# Main.net
KiCad netlist of a schematic drawn in Altium Designer
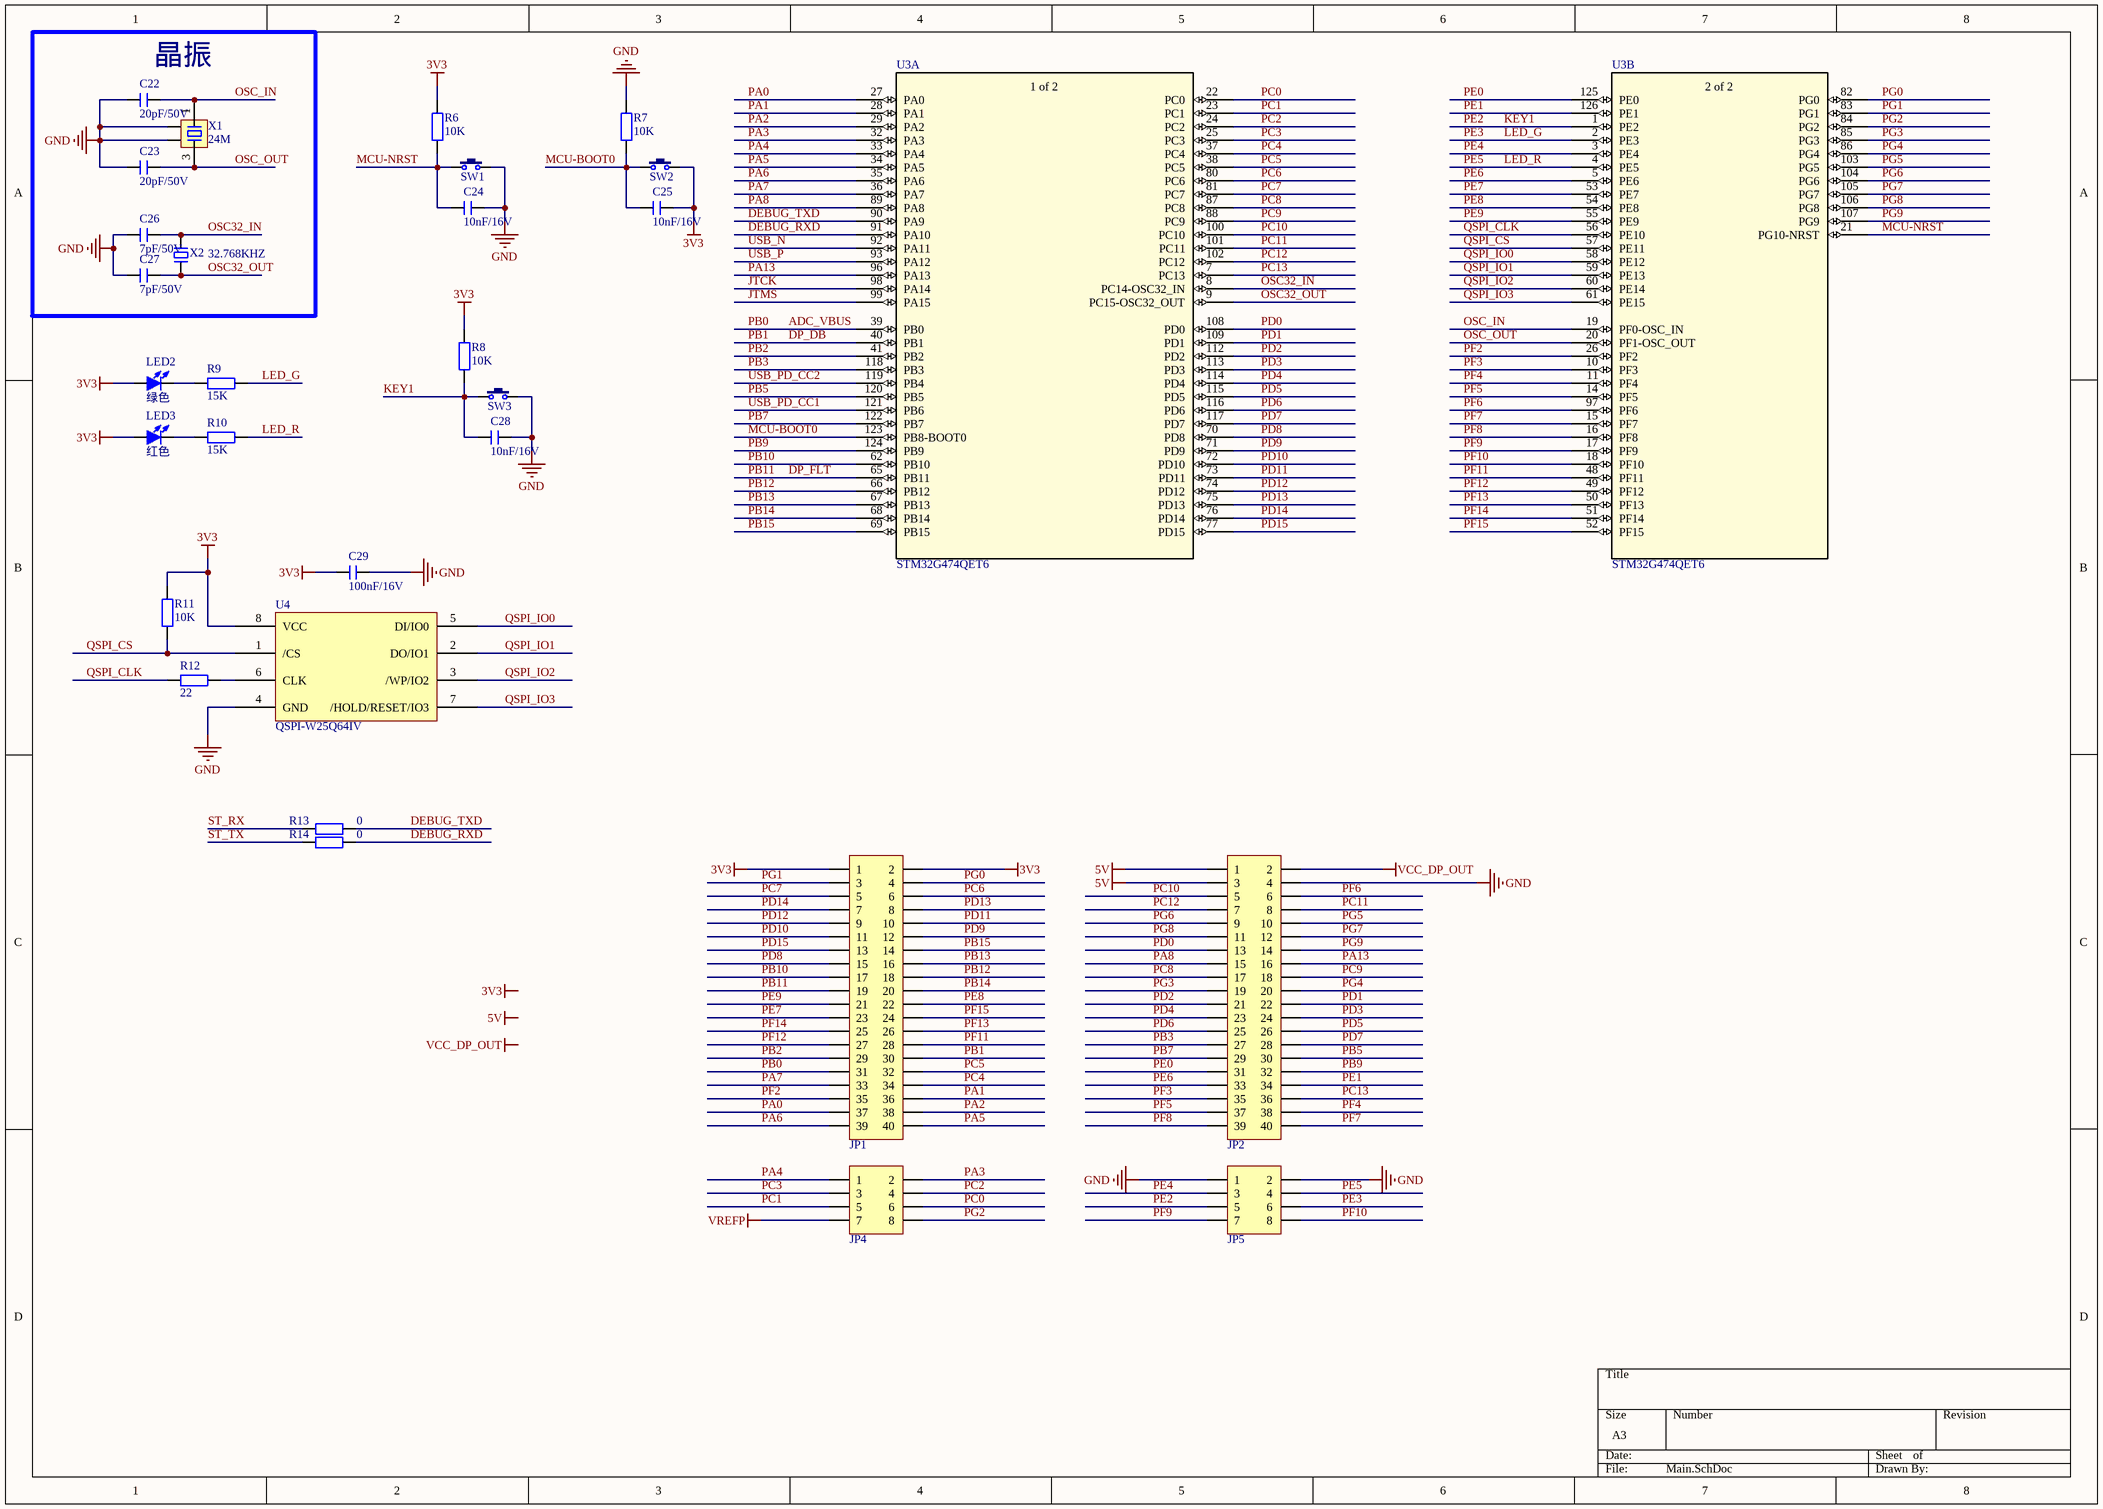
[diagram p0: Main.SchDoc]

(export (version "E")
  (design (tool "Eeschema 10.0.6"))
  (components
    (comp (ref "C22")
      (value "20pF/50V")
      (footprint "C 0402_L")
      (description "贴片电容")
      (libsource (lib "3.1   - 电阻-电容-电感") (part "C"))
    )
    (comp (ref "C23")
      (value "20pF/50V")
      (footprint "C 0402_L")
      (description "贴片电容")
      (libsource (lib "3.1   - 电阻-电容-电感") (part "C"))
    )
    (comp (ref "C24")
      (value "10nF/16V")
      (footprint "C 0402_L")
      (description "贴片电容")
      (libsource (lib "3.1   - 电阻-电容-电感") (part "C"))
    )
    (comp (ref "C25")
      (value "10nF/16V")
      (footprint "C 0402_L")
      (description "贴片电容")
      (libsource (lib "3.1   - 电阻-电容-电感") (part "C"))
    )
    (comp (ref "C26")
      (value "7pF/50V")
      (footprint "C 0402_L")
      (description "贴片电容")
      (libsource (lib "3.1   - 电阻-电容-电感") (part "C"))
    )
    (comp (ref "C27")
      (value "7pF/50V")
      (footprint "C 0402_L")
      (description "贴片电容")
      (libsource (lib "3.1   - 电阻-电容-电感") (part "C"))
    )
    (comp (ref "C28")
      (value "10nF/16V")
      (footprint "C 0402_L")
      (description "贴片电容")
      (libsource (lib "3.1   - 电阻-电容-电感") (part "C"))
    )
    (comp (ref "C29")
      (value "100nF/16V")
      (footprint "C 0402_L")
      (description "贴片电容")
      (libsource (lib "3.1   - 电阻-电容-电感") (part "C"))
    )
    (comp (ref "JP1")
      (value "Header 2X11")
      (footprint "HDR2.54-LI-2x20P")
      (description "20*2P接插件")
      (fields (field (name "版权归属") "源创客"))
      (libsource (lib "4.5   - 接插件-脚距2.54") (part "Header 20X2"))
    )
    (comp (ref "JP2")
      (value "Header 2X11")
      (footprint "HDR2.54-LI-2x20P")
      (description "20*2P接插件")
      (fields (field (name "版权归属") "源创客"))
      (libsource (lib "4.5   - 接插件-脚距2.54") (part "Header 20X2"))
    )
    (comp (ref "JP4")
      (value "Header 4X2")
      (footprint "HDR2.54-LI-2x4P")
      (description "4*2P接插件")
      (fields (field (name "版权归属") "源创客"))
      (libsource (lib "4.5   - 接插件-脚距2.54") (part "Header 4X2"))
    )
    (comp (ref "JP5")
      (value "Header 4X2")
      (footprint "HDR2.54-LI-2x4P")
      (description "4*2P接插件")
      (fields (field (name "版权归属") "源创客"))
      (libsource (lib "4.5   - 接插件-脚距2.54") (part "Header 4X2"))
    )
    (comp (ref "LED2")
      (value "绿色")
      (footprint "LED")
      (description "C84267")
      (libsource (lib "9.1   - LED") (part "LED-SMD"))
    )
    (comp (ref "LED3")
      (value "红色")
      (footprint "LED")
      (description "C84267")
      (libsource (lib "9.1   - LED") (part "LED-SMD"))
    )
    (comp (ref "R6")
      (value "10K")
      (footprint "R 0402_L")
      (description "贴片电阻")
      (libsource (lib "3.1   - 电阻-电容-电感") (part "R"))
    )
    (comp (ref "R7")
      (value "10K")
      (footprint "R 0402_L")
      (description "贴片电阻")
      (libsource (lib "3.1   - 电阻-电容-电感") (part "R"))
    )
    (comp (ref "R8")
      (value "10K")
      (footprint "R 0402_L")
      (description "贴片电阻")
      (libsource (lib "3.1   - 电阻-电容-电感") (part "R"))
    )
    (comp (ref "R9")
      (value "15K")
      (footprint "R 0402_L")
      (description "贴片电阻 0402 5%")
      (libsource (lib "3.1   - 电阻-电容-电感") (part "R"))
    )
    (comp (ref "R10")
      (value "15K")
      (footprint "R 0402_L")
      (description "贴片电阻 0402 5%")
      (libsource (lib "3.1   - 电阻-电容-电感") (part "R"))
    )
    (comp (ref "R11")
      (value "10K")
      (footprint "R 0402_L")
      (description "贴片电阻 0402 1%")
      (libsource (lib "3.1   - 电阻-电容-电感") (part "R"))
    )
    (comp (ref "R12")
      (value "22")
      (footprint "R 0402_L")
      (description "贴片电阻 0402 1%")
      (libsource (lib "3.1   - 电阻-电容-电感") (part "R"))
    )
    (comp (ref "R13")
      (value "0")
      (footprint "R 0402_L")
      (description "贴片电阻")
      (libsource (lib "3.1   - 电阻-电容-电感") (part "R"))
    )
    (comp (ref "R14")
      (value "0")
      (footprint "R 0402_L")
      (description "贴片电阻")
      (libsource (lib "3.1   - 电阻-电容-电感") (part "R"))
    )
    (comp (ref "SW1")
      (value "3x6x5")
      (footprint "按钮")
      (description "3x6轻触开关")
      (libsource (lib "5.1   - 按键-开关") (part "TSW 3x6"))
    )
    (comp (ref "SW2")
      (value "3x6x5")
      (footprint "按钮")
      (description "3x6轻触开关")
      (libsource (lib "5.1   - 按键-开关") (part "TSW 3x6"))
    )
    (comp (ref "SW3")
      (value "3x6x5")
      (footprint "按钮")
      (description "3x6轻触开关")
      (libsource (lib "5.1   - 按键-开关") (part "TSW 3x6"))
    )
    (comp (ref "U3")
      (value "STM32G474QET6")
      (footprint "LQFP128-14*14")
      (description "No Description Available")
      (libsource (lib "2021-04-22_13-53-57") (part "STM32G474QET6"))
    )
    (comp (ref "U4")
      (value "QSPI-W25Q64IV")
      (footprint "SOP8")
      (libsource (lib "AltiumV15") (part "QSPI-W25Q256IV"))
    )
    (comp (ref "X1")
      (value "24M")
      (footprint "OSC 3225-4P")
      (description "4脚无源晶振")
      (libsource (lib "10.1 - 保险丝-晶振") (part "XTAL-4P"))
    )
    (comp (ref "X2")
      (value "32.768KHZ")
      (footprint "OSC 3215-2P")
      (description "2脚无源脚晶振")
      (libsource (lib "10.1 - 保险丝-晶振") (part "XTAL-2P"))
    )
  )
  (nets
    (net (code "1") (name "/ADC_VBUS") (class "Default")
      (node (ref "JP1") (pin "31") (pinfunction "31_31") (pintype "passive"))
      (node (ref "U3") (pin "39") (pinfunction "PB0_39") (pintype "bidirectional"))
    )
    (net (code "2") (name "/DEBUG_RXD") (class "Default")
      (node (ref "R14") (pin "2") (pinfunction "2_2") (pintype "passive"))
      (node (ref "U3") (pin "91") (pinfunction "PA10_91") (pintype "bidirectional"))
    )
    (net (code "3") (name "/DEBUG_TXD") (class "Default")
      (node (ref "R13") (pin "2") (pinfunction "2_2") (pintype "passive"))
      (node (ref "U3") (pin "90") (pinfunction "PA9_90") (pintype "bidirectional"))
    )
    (net (code "4") (name "/DP_DB") (class "Default")
      (node (ref "JP1") (pin "30") (pinfunction "30_30") (pintype "passive"))
      (node (ref "U3") (pin "40") (pinfunction "PB1_40") (pintype "bidirectional"))
    )
    (net (code "5") (name "/DP_FLT") (class "Default")
      (node (ref "JP1") (pin "19") (pinfunction "19_19") (pintype "passive"))
      (node (ref "U3") (pin "65") (pinfunction "PB11_65") (pintype "bidirectional"))
    )
    (net (code "6") (name "/JTCK") (class "Default")
      (node (ref "U3") (pin "98") (pinfunction "PA14_98") (pintype "bidirectional"))
    )
    (net (code "7") (name "/JTMS") (class "Default")
      (node (ref "U3") (pin "99") (pinfunction "PA15_99") (pintype "bidirectional"))
    )
    (net (code "8") (name "/KEY1") (class "Default")
      (node (ref "C28") (pin "1") (pinfunction "1_1") (pintype "passive"))
      (node (ref "JP5") (pin "5") (pinfunction "5_5") (pintype "passive"))
      (node (ref "R8") (pin "1") (pinfunction "1_1") (pintype "passive"))
      (node (ref "SW3") (pin "1") (pinfunction "1_1") (pintype "passive"))
      (node (ref "U3") (pin "1") (pinfunction "PE2_1") (pintype "bidirectional"))
    )
    (net (code "9") (name "/LED_G") (class "Default")
      (node (ref "JP5") (pin "6") (pinfunction "6_6") (pintype "passive"))
      (node (ref "R9") (pin "1") (pinfunction "1_1") (pintype "passive"))
      (node (ref "U3") (pin "2") (pinfunction "PE3_2") (pintype "bidirectional"))
    )
    (net (code "10") (name "/LED_R") (class "Default")
      (node (ref "JP5") (pin "4") (pinfunction "4_4") (pintype "passive"))
      (node (ref "R10") (pin "1") (pinfunction "1_1") (pintype "passive"))
      (node (ref "U3") (pin "4") (pinfunction "PE5_4") (pintype "bidirectional"))
    )
    (net (code "11") (name "/MCU-BOOT0") (class "Default")
      (node (ref "C25") (pin "1") (pinfunction "1_1") (pintype "passive"))
      (node (ref "R7") (pin "1") (pinfunction "1_1") (pintype "passive"))
      (node (ref "SW2") (pin "1") (pinfunction "1_1") (pintype "passive"))
      (node (ref "U3") (pin "123") (pinfunction "PB8-BOOT0_123") (pintype "bidirectional"))
    )
    (net (code "12") (name "/MCU-NRST") (class "Default")
      (node (ref "C24") (pin "1") (pinfunction "1_1") (pintype "passive"))
      (node (ref "R6") (pin "1") (pinfunction "1_1") (pintype "passive"))
      (node (ref "SW1") (pin "1") (pinfunction "1_1") (pintype "passive"))
      (node (ref "U3") (pin "21") (pinfunction "PG10-NRST_21") (pintype "bidirectional"))
    )
    (net (code "13") (name "/OSC32_IN") (class "Default")
      (node (ref "C26") (pin "2") (pinfunction "2_2") (pintype "passive"))
      (node (ref "U3") (pin "8") (pinfunction "PC14-OSC32_IN_8") (pintype "bidirectional"))
      (node (ref "X2") (pin "2") (pinfunction "2_2") (pintype "passive"))
    )
    (net (code "14") (name "/OSC32_OUT") (class "Default")
      (node (ref "C27") (pin "2") (pinfunction "2_2") (pintype "passive"))
      (node (ref "U3") (pin "9") (pinfunction "PC15-OSC32_OUT_9") (pintype "bidirectional"))
      (node (ref "X2") (pin "1") (pinfunction "1_1") (pintype "passive"))
    )
    (net (code "15") (name "/OSC_IN") (class "Default")
      (node (ref "C22") (pin "2") (pinfunction "2_2") (pintype "passive"))
      (node (ref "U3") (pin "19") (pinfunction "PF0-OSC_IN_19") (pintype "bidirectional"))
      (node (ref "X1") (pin "1") (pinfunction "1_1") (pintype "passive"))
    )
    (net (code "16") (name "/OSC_OUT") (class "Default")
      (node (ref "C23") (pin "2") (pinfunction "2_2") (pintype "passive"))
      (node (ref "U3") (pin "20") (pinfunction "PF1-OSC_OUT_20") (pintype "bidirectional"))
      (node (ref "X1") (pin "3") (pinfunction "3_3") (pintype "passive"))
    )
    (net (code "17") (name "/PA0") (class "Default")
      (node (ref "JP1") (pin "37") (pinfunction "37_37") (pintype "passive"))
      (node (ref "U3") (pin "27") (pinfunction "PA0_27") (pintype "bidirectional"))
    )
    (net (code "18") (name "/PA1") (class "Default")
      (node (ref "JP1") (pin "36") (pinfunction "36_36") (pintype "passive"))
      (node (ref "U3") (pin "28") (pinfunction "PA1_28") (pintype "bidirectional"))
    )
    (net (code "19") (name "/PA2") (class "Default")
      (node (ref "JP1") (pin "38") (pinfunction "38_38") (pintype "passive"))
      (node (ref "U3") (pin "29") (pinfunction "PA2_29") (pintype "bidirectional"))
    )
    (net (code "20") (name "/PA3") (class "Default")
      (node (ref "JP4") (pin "2") (pinfunction "2_2") (pintype "passive"))
      (node (ref "U3") (pin "32") (pinfunction "PA3_32") (pintype "bidirectional"))
    )
    (net (code "21") (name "/PA4") (class "Default")
      (node (ref "JP4") (pin "1") (pinfunction "1_1") (pintype "passive"))
      (node (ref "U3") (pin "33") (pinfunction "PA4_33") (pintype "bidirectional"))
    )
    (net (code "22") (name "/PA5") (class "Default")
      (node (ref "JP1") (pin "40") (pinfunction "40_40") (pintype "passive"))
      (node (ref "U3") (pin "34") (pinfunction "PA5_34") (pintype "bidirectional"))
    )
    (net (code "23") (name "/PA6") (class "Default")
      (node (ref "JP1") (pin "39") (pinfunction "39_39") (pintype "passive"))
      (node (ref "U3") (pin "35") (pinfunction "PA6_35") (pintype "bidirectional"))
    )
    (net (code "24") (name "/PA7") (class "Default")
      (node (ref "JP1") (pin "33") (pinfunction "33_33") (pintype "passive"))
      (node (ref "U3") (pin "36") (pinfunction "PA7_36") (pintype "bidirectional"))
    )
    (net (code "25") (name "/PA8") (class "Default")
      (node (ref "JP2") (pin "15") (pinfunction "15_15") (pintype "passive"))
      (node (ref "U3") (pin "89") (pinfunction "PA8_89") (pintype "bidirectional"))
    )
    (net (code "26") (name "/PA13") (class "Default")
      (node (ref "JP2") (pin "16") (pinfunction "16_16") (pintype "passive"))
      (node (ref "U3") (pin "96") (pinfunction "PA13_96") (pintype "bidirectional"))
    )
    (net (code "27") (name "/PB2") (class "Default")
      (node (ref "JP1") (pin "29") (pinfunction "29_29") (pintype "passive"))
      (node (ref "U3") (pin "41") (pinfunction "PB2_41") (pintype "bidirectional"))
    )
    (net (code "28") (name "/PB3") (class "Default")
      (node (ref "JP2") (pin "27") (pinfunction "27_27") (pintype "passive"))
      (node (ref "U3") (pin "118") (pinfunction "PB3_118") (pintype "bidirectional"))
    )
    (net (code "29") (name "/PB5") (class "Default")
      (node (ref "JP2") (pin "30") (pinfunction "30_30") (pintype "passive"))
      (node (ref "U3") (pin "120") (pinfunction "PB5_120") (pintype "bidirectional"))
    )
    (net (code "30") (name "/PB7") (class "Default")
      (node (ref "JP2") (pin "29") (pinfunction "29_29") (pintype "passive"))
      (node (ref "U3") (pin "122") (pinfunction "PB7_122") (pintype "bidirectional"))
    )
    (net (code "31") (name "/PB9") (class "Default")
      (node (ref "JP2") (pin "32") (pinfunction "32_32") (pintype "passive"))
      (node (ref "U3") (pin "124") (pinfunction "PB9_124") (pintype "bidirectional"))
    )
    (net (code "32") (name "/PB10") (class "Default")
      (node (ref "JP1") (pin "17") (pinfunction "17_17") (pintype "passive"))
      (node (ref "U3") (pin "62") (pinfunction "PB10_62") (pintype "bidirectional"))
    )
    (net (code "33") (name "/PB12") (class "Default")
      (node (ref "JP1") (pin "18") (pinfunction "18_18") (pintype "passive"))
      (node (ref "U3") (pin "66") (pinfunction "PB12_66") (pintype "bidirectional"))
    )
    (net (code "34") (name "/PB13") (class "Default")
      (node (ref "JP1") (pin "16") (pinfunction "16_16") (pintype "passive"))
      (node (ref "U3") (pin "67") (pinfunction "PB13_67") (pintype "bidirectional"))
    )
    (net (code "35") (name "/PB14") (class "Default")
      (node (ref "JP1") (pin "20") (pinfunction "20_20") (pintype "passive"))
      (node (ref "U3") (pin "68") (pinfunction "PB14_68") (pintype "bidirectional"))
    )
    (net (code "36") (name "/PB15") (class "Default")
      (node (ref "JP1") (pin "14") (pinfunction "14_14") (pintype "passive"))
      (node (ref "U3") (pin "69") (pinfunction "PB15_69") (pintype "bidirectional"))
    )
    (net (code "37") (name "/PC0") (class "Default")
      (node (ref "JP4") (pin "6") (pinfunction "6_6") (pintype "passive"))
      (node (ref "U3") (pin "22") (pinfunction "PC0_22") (pintype "bidirectional"))
    )
    (net (code "38") (name "/PC1") (class "Default")
      (node (ref "JP4") (pin "5") (pinfunction "5_5") (pintype "passive"))
      (node (ref "U3") (pin "23") (pinfunction "PC1_23") (pintype "bidirectional"))
    )
    (net (code "39") (name "/PC2") (class "Default")
      (node (ref "JP4") (pin "4") (pinfunction "4_4") (pintype "passive"))
      (node (ref "U3") (pin "24") (pinfunction "PC2_24") (pintype "bidirectional"))
    )
    (net (code "40") (name "/PC3") (class "Default")
      (node (ref "JP4") (pin "3") (pinfunction "3_3") (pintype "passive"))
      (node (ref "U3") (pin "25") (pinfunction "PC3_25") (pintype "bidirectional"))
    )
    (net (code "41") (name "/PC4") (class "Default")
      (node (ref "JP1") (pin "34") (pinfunction "34_34") (pintype "passive"))
      (node (ref "U3") (pin "37") (pinfunction "PC4_37") (pintype "bidirectional"))
    )
    (net (code "42") (name "/PC5") (class "Default")
      (node (ref "JP1") (pin "32") (pinfunction "32_32") (pintype "passive"))
      (node (ref "U3") (pin "38") (pinfunction "PC5_38") (pintype "bidirectional"))
    )
    (net (code "43") (name "/PC6") (class "Default")
      (node (ref "JP1") (pin "6") (pinfunction "6_6") (pintype "passive"))
      (node (ref "U3") (pin "80") (pinfunction "PC6_80") (pintype "bidirectional"))
    )
    (net (code "44") (name "/PC7") (class "Default")
      (node (ref "JP1") (pin "5") (pinfunction "5_5") (pintype "passive"))
      (node (ref "U3") (pin "81") (pinfunction "PC7_81") (pintype "bidirectional"))
    )
    (net (code "45") (name "/PC8") (class "Default")
      (node (ref "JP2") (pin "17") (pinfunction "17_17") (pintype "passive"))
      (node (ref "U3") (pin "87") (pinfunction "PC8_87") (pintype "bidirectional"))
    )
    (net (code "46") (name "/PC9") (class "Default")
      (node (ref "JP2") (pin "18") (pinfunction "18_18") (pintype "passive"))
      (node (ref "U3") (pin "88") (pinfunction "PC9_88") (pintype "bidirectional"))
    )
    (net (code "47") (name "/PC10") (class "Default")
      (node (ref "JP2") (pin "5") (pinfunction "5_5") (pintype "passive"))
      (node (ref "U3") (pin "100") (pinfunction "PC10_100") (pintype "bidirectional"))
    )
    (net (code "48") (name "/PC11") (class "Default")
      (node (ref "JP2") (pin "8") (pinfunction "8_8") (pintype "passive"))
      (node (ref "U3") (pin "101") (pinfunction "PC11_101") (pintype "bidirectional"))
    )
    (net (code "49") (name "/PC12") (class "Default")
      (node (ref "JP2") (pin "7") (pinfunction "7_7") (pintype "passive"))
      (node (ref "U3") (pin "102") (pinfunction "PC12_102") (pintype "bidirectional"))
    )
    (net (code "50") (name "/PC13") (class "Default")
      (node (ref "JP2") (pin "36") (pinfunction "36_36") (pintype "passive"))
      (node (ref "U3") (pin "7") (pinfunction "PC13_7") (pintype "bidirectional"))
    )
    (net (code "51") (name "/PD0") (class "Default")
      (node (ref "JP2") (pin "13") (pinfunction "13_13") (pintype "passive"))
      (node (ref "U3") (pin "108") (pinfunction "PD0_108") (pintype "bidirectional"))
    )
    (net (code "52") (name "/PD1") (class "Default")
      (node (ref "JP2") (pin "22") (pinfunction "22_22") (pintype "passive"))
      (node (ref "U3") (pin "109") (pinfunction "PD1_109") (pintype "bidirectional"))
    )
    (net (code "53") (name "/PD2") (class "Default")
      (node (ref "JP2") (pin "21") (pinfunction "21_21") (pintype "passive"))
      (node (ref "U3") (pin "112") (pinfunction "PD2_112") (pintype "bidirectional"))
    )
    (net (code "54") (name "/PD3") (class "Default")
      (node (ref "JP2") (pin "24") (pinfunction "24_24") (pintype "passive"))
      (node (ref "U3") (pin "113") (pinfunction "PD3_113") (pintype "bidirectional"))
    )
    (net (code "55") (name "/PD4") (class "Default")
      (node (ref "JP2") (pin "23") (pinfunction "23_23") (pintype "passive"))
      (node (ref "U3") (pin "114") (pinfunction "PD4_114") (pintype "bidirectional"))
    )
    (net (code "56") (name "/PD5") (class "Default")
      (node (ref "JP2") (pin "26") (pinfunction "26_26") (pintype "passive"))
      (node (ref "U3") (pin "115") (pinfunction "PD5_115") (pintype "bidirectional"))
    )
    (net (code "57") (name "/PD6") (class "Default")
      (node (ref "JP2") (pin "25") (pinfunction "25_25") (pintype "passive"))
      (node (ref "U3") (pin "116") (pinfunction "PD6_116") (pintype "bidirectional"))
    )
    (net (code "58") (name "/PD7") (class "Default")
      (node (ref "JP2") (pin "28") (pinfunction "28_28") (pintype "passive"))
      (node (ref "U3") (pin "117") (pinfunction "PD7_117") (pintype "bidirectional"))
    )
    (net (code "59") (name "/PD8") (class "Default")
      (node (ref "JP1") (pin "15") (pinfunction "15_15") (pintype "passive"))
      (node (ref "U3") (pin "70") (pinfunction "PD8_70") (pintype "bidirectional"))
    )
    (net (code "60") (name "/PD9") (class "Default")
      (node (ref "JP1") (pin "12") (pinfunction "12_12") (pintype "passive"))
      (node (ref "U3") (pin "71") (pinfunction "PD9_71") (pintype "bidirectional"))
    )
    (net (code "61") (name "/PD10") (class "Default")
      (node (ref "JP1") (pin "11") (pinfunction "11_11") (pintype "passive"))
      (node (ref "U3") (pin "72") (pinfunction "PD10_72") (pintype "bidirectional"))
    )
    (net (code "62") (name "/PD11") (class "Default")
      (node (ref "JP1") (pin "10") (pinfunction "10_10") (pintype "passive"))
      (node (ref "U3") (pin "73") (pinfunction "PD11_73") (pintype "bidirectional"))
    )
    (net (code "63") (name "/PD12") (class "Default")
      (node (ref "JP1") (pin "9") (pinfunction "9_9") (pintype "passive"))
      (node (ref "U3") (pin "74") (pinfunction "PD12_74") (pintype "bidirectional"))
    )
    (net (code "64") (name "/PD13") (class "Default")
      (node (ref "JP1") (pin "8") (pinfunction "8_8") (pintype "passive"))
      (node (ref "U3") (pin "75") (pinfunction "PD13_75") (pintype "bidirectional"))
    )
    (net (code "65") (name "/PD14") (class "Default")
      (node (ref "JP1") (pin "7") (pinfunction "7_7") (pintype "passive"))
      (node (ref "U3") (pin "76") (pinfunction "PD14_76") (pintype "bidirectional"))
    )
    (net (code "66") (name "/PD15") (class "Default")
      (node (ref "JP1") (pin "13") (pinfunction "13_13") (pintype "passive"))
      (node (ref "U3") (pin "77") (pinfunction "PD15_77") (pintype "bidirectional"))
    )
    (net (code "67") (name "/PE0") (class "Default")
      (node (ref "JP2") (pin "31") (pinfunction "31_31") (pintype "passive"))
      (node (ref "U3") (pin "125") (pinfunction "PE0_125") (pintype "bidirectional"))
    )
    (net (code "68") (name "/PE1") (class "Default")
      (node (ref "JP2") (pin "34") (pinfunction "34_34") (pintype "passive"))
      (node (ref "U3") (pin "126") (pinfunction "PE1_126") (pintype "bidirectional"))
    )
    (net (code "69") (name "/PE4") (class "Default")
      (node (ref "JP5") (pin "3") (pinfunction "3_3") (pintype "passive"))
      (node (ref "U3") (pin "3") (pinfunction "PE4_3") (pintype "bidirectional"))
    )
    (net (code "70") (name "/PE6") (class "Default")
      (node (ref "JP2") (pin "33") (pinfunction "33_33") (pintype "passive"))
      (node (ref "U3") (pin "5") (pinfunction "PE6_5") (pintype "bidirectional"))
    )
    (net (code "71") (name "/PE7") (class "Default")
      (node (ref "JP1") (pin "23") (pinfunction "23_23") (pintype "passive"))
      (node (ref "U3") (pin "53") (pinfunction "PE7_53") (pintype "bidirectional"))
    )
    (net (code "72") (name "/PE8") (class "Default")
      (node (ref "JP1") (pin "22") (pinfunction "22_22") (pintype "passive"))
      (node (ref "U3") (pin "54") (pinfunction "PE8_54") (pintype "bidirectional"))
    )
    (net (code "73") (name "/PE9") (class "Default")
      (node (ref "JP1") (pin "21") (pinfunction "21_21") (pintype "passive"))
      (node (ref "U3") (pin "55") (pinfunction "PE9_55") (pintype "bidirectional"))
    )
    (net (code "74") (name "/PF2") (class "Default")
      (node (ref "JP1") (pin "35") (pinfunction "35_35") (pintype "passive"))
      (node (ref "U3") (pin "26") (pinfunction "PF2_26") (pintype "bidirectional"))
    )
    (net (code "75") (name "/PF3") (class "Default")
      (node (ref "JP2") (pin "35") (pinfunction "35_35") (pintype "passive"))
      (node (ref "U3") (pin "10") (pinfunction "PF3_10") (pintype "bidirectional"))
    )
    (net (code "76") (name "/PF4") (class "Default")
      (node (ref "JP2") (pin "38") (pinfunction "38_38") (pintype "passive"))
      (node (ref "U3") (pin "11") (pinfunction "PF4_11") (pintype "bidirectional"))
    )
    (net (code "77") (name "/PF5") (class "Default")
      (node (ref "JP2") (pin "37") (pinfunction "37_37") (pintype "passive"))
      (node (ref "U3") (pin "14") (pinfunction "PF5_14") (pintype "bidirectional"))
    )
    (net (code "78") (name "/PF6") (class "Default")
      (node (ref "JP2") (pin "6") (pinfunction "6_6") (pintype "passive"))
      (node (ref "U3") (pin "97") (pinfunction "PF6_97") (pintype "bidirectional"))
    )
    (net (code "79") (name "/PF7") (class "Default")
      (node (ref "JP2") (pin "40") (pinfunction "40_40") (pintype "passive"))
      (node (ref "U3") (pin "15") (pinfunction "PF7_15") (pintype "bidirectional"))
    )
    (net (code "80") (name "/PF8") (class "Default")
      (node (ref "JP2") (pin "39") (pinfunction "39_39") (pintype "passive"))
      (node (ref "U3") (pin "16") (pinfunction "PF8_16") (pintype "bidirectional"))
    )
    (net (code "81") (name "/PF9") (class "Default")
      (node (ref "JP5") (pin "7") (pinfunction "7_7") (pintype "passive"))
      (node (ref "U3") (pin "17") (pinfunction "PF9_17") (pintype "bidirectional"))
    )
    (net (code "82") (name "/PF10") (class "Default")
      (node (ref "JP5") (pin "8") (pinfunction "8_8") (pintype "passive"))
      (node (ref "U3") (pin "18") (pinfunction "PF10_18") (pintype "bidirectional"))
    )
    (net (code "83") (name "/PF11") (class "Default")
      (node (ref "JP1") (pin "28") (pinfunction "28_28") (pintype "passive"))
      (node (ref "U3") (pin "48") (pinfunction "PF11_48") (pintype "bidirectional"))
    )
    (net (code "84") (name "/PF12") (class "Default")
      (node (ref "JP1") (pin "27") (pinfunction "27_27") (pintype "passive"))
      (node (ref "U3") (pin "49") (pinfunction "PF12_49") (pintype "bidirectional"))
    )
    (net (code "85") (name "/PF13") (class "Default")
      (node (ref "JP1") (pin "26") (pinfunction "26_26") (pintype "passive"))
      (node (ref "U3") (pin "50") (pinfunction "PF13_50") (pintype "bidirectional"))
    )
    (net (code "86") (name "/PF14") (class "Default")
      (node (ref "JP1") (pin "25") (pinfunction "25_25") (pintype "passive"))
      (node (ref "U3") (pin "51") (pinfunction "PF14_51") (pintype "bidirectional"))
    )
    (net (code "87") (name "/PF15") (class "Default")
      (node (ref "JP1") (pin "24") (pinfunction "24_24") (pintype "passive"))
      (node (ref "U3") (pin "52") (pinfunction "PF15_52") (pintype "bidirectional"))
    )
    (net (code "88") (name "/PG0") (class "Default")
      (node (ref "JP1") (pin "4") (pinfunction "4_4") (pintype "passive"))
      (node (ref "U3") (pin "82") (pinfunction "PG0_82") (pintype "bidirectional"))
    )
    (net (code "89") (name "/PG1") (class "Default")
      (node (ref "JP1") (pin "3") (pinfunction "3_3") (pintype "passive"))
      (node (ref "U3") (pin "83") (pinfunction "PG1_83") (pintype "bidirectional"))
    )
    (net (code "90") (name "/PG2") (class "Default")
      (node (ref "JP4") (pin "8") (pinfunction "8_8") (pintype "passive"))
      (node (ref "U3") (pin "84") (pinfunction "PG2_84") (pintype "bidirectional"))
    )
    (net (code "91") (name "/PG3") (class "Default")
      (node (ref "JP2") (pin "19") (pinfunction "19_19") (pintype "passive"))
      (node (ref "U3") (pin "85") (pinfunction "PG3_85") (pintype "bidirectional"))
    )
    (net (code "92") (name "/PG4") (class "Default")
      (node (ref "JP2") (pin "20") (pinfunction "20_20") (pintype "passive"))
      (node (ref "U3") (pin "86") (pinfunction "PG4_86") (pintype "bidirectional"))
    )
    (net (code "93") (name "/PG5") (class "Default")
      (node (ref "JP2") (pin "10") (pinfunction "10_10") (pintype "passive"))
      (node (ref "U3") (pin "103") (pinfunction "PG5_103") (pintype "bidirectional"))
    )
    (net (code "94") (name "/PG6") (class "Default")
      (node (ref "JP2") (pin "9") (pinfunction "9_9") (pintype "passive"))
      (node (ref "U3") (pin "104") (pinfunction "PG6_104") (pintype "bidirectional"))
    )
    (net (code "95") (name "/PG7") (class "Default")
      (node (ref "JP2") (pin "12") (pinfunction "12_12") (pintype "passive"))
      (node (ref "U3") (pin "105") (pinfunction "PG7_105") (pintype "bidirectional"))
    )
    (net (code "96") (name "/PG8") (class "Default")
      (node (ref "JP2") (pin "11") (pinfunction "11_11") (pintype "passive"))
      (node (ref "U3") (pin "106") (pinfunction "PG8_106") (pintype "bidirectional"))
    )
    (net (code "97") (name "/PG9") (class "Default")
      (node (ref "JP2") (pin "14") (pinfunction "14_14") (pintype "passive"))
      (node (ref "U3") (pin "107") (pinfunction "PG9_107") (pintype "bidirectional"))
    )
    (net (code "98") (name "/QSPI_CLK") (class "Default")
      (node (ref "R12") (pin "1") (pinfunction "1_1") (pintype "passive"))
      (node (ref "U3") (pin "56") (pinfunction "PE10_56") (pintype "bidirectional"))
    )
    (net (code "99") (name "/QSPI_CS") (class "Default")
      (node (ref "R11") (pin "2") (pinfunction "2_2") (pintype "passive"))
      (node (ref "U3") (pin "57") (pinfunction "PE11_57") (pintype "bidirectional"))
      (node (ref "U4") (pin "1") (pinfunction "/CS_1") (pintype "passive"))
    )
    (net (code "100") (name "/QSPI_IO0") (class "Default")
      (node (ref "U3") (pin "58") (pinfunction "PE12_58") (pintype "bidirectional"))
      (node (ref "U4") (pin "5") (pinfunction "DI/IO0_5") (pintype "passive"))
    )
    (net (code "101") (name "/QSPI_IO1") (class "Default")
      (node (ref "U3") (pin "59") (pinfunction "PE13_59") (pintype "bidirectional"))
      (node (ref "U4") (pin "2") (pinfunction "DO/IO1_2") (pintype "passive"))
    )
    (net (code "102") (name "/QSPI_IO2") (class "Default")
      (node (ref "U3") (pin "60") (pinfunction "PE14_60") (pintype "bidirectional"))
      (node (ref "U4") (pin "3") (pinfunction "/WP/IO2_3") (pintype "passive"))
    )
    (net (code "103") (name "/QSPI_IO3") (class "Default")
      (node (ref "U3") (pin "61") (pinfunction "PE15_61") (pintype "bidirectional"))
      (node (ref "U4") (pin "7") (pinfunction "/HOLD/RESET/IO3_7") (pintype "passive"))
    )
    (net (code "104") (name "/ST_RX") (class "Default")
      (node (ref "R13") (pin "1") (pinfunction "1_1") (pintype "passive"))
    )
    (net (code "105") (name "/ST_TX") (class "Default")
      (node (ref "R14") (pin "1") (pinfunction "1_1") (pintype "passive"))
    )
    (net (code "106") (name "/USB_N") (class "Default")
      (node (ref "U3") (pin "92") (pinfunction "PA11_92") (pintype "bidirectional"))
    )
    (net (code "107") (name "/USB_P") (class "Default")
      (node (ref "U3") (pin "93") (pinfunction "PA12_93") (pintype "bidirectional"))
    )
    (net (code "108") (name "/USB_PD_CC1") (class "Default")
      (node (ref "U3") (pin "121") (pinfunction "PB6_121") (pintype "bidirectional"))
    )
    (net (code "109") (name "/USB_PD_CC2") (class "Default")
      (node (ref "U3") (pin "119") (pinfunction "PB4_119") (pintype "bidirectional"))
    )
    (net (code "110") (name "3V3") (class "Default")
      (node (ref "C25") (pin "2") (pinfunction "2_2") (pintype "passive"))
      (node (ref "C29") (pin "2") (pinfunction "2_2") (pintype "passive"))
      (node (ref "JP1") (pin "1") (pinfunction "1_1") (pintype "passive"))
      (node (ref "JP1") (pin "2") (pinfunction "2_2") (pintype "passive"))
      (node (ref "LED2") (pin "1") (pinfunction "A_1") (pintype "passive"))
      (node (ref "LED3") (pin "1") (pinfunction "A_1") (pintype "passive"))
      (node (ref "R11") (pin "1") (pinfunction "1_1") (pintype "passive"))
      (node (ref "R6") (pin "2") (pinfunction "2_2") (pintype "passive"))
      (node (ref "R8") (pin "2") (pinfunction "2_2") (pintype "passive"))
      (node (ref "SW2") (pin "2") (pinfunction "2_2") (pintype "passive"))
      (node (ref "U4") (pin "8") (pinfunction "VCC_8") (pintype "passive"))
    )
    (net (code "111") (name "5V") (class "Default")
      (node (ref "JP2") (pin "1") (pinfunction "1_1") (pintype "passive"))
      (node (ref "JP2") (pin "3") (pinfunction "3_3") (pintype "passive"))
    )
    (net (code "112") (name "GND") (class "Default")
      (node (ref "C22") (pin "1") (pinfunction "1_1") (pintype "passive"))
      (node (ref "C23") (pin "1") (pinfunction "1_1") (pintype "passive"))
      (node (ref "C24") (pin "2") (pinfunction "2_2") (pintype "passive"))
      (node (ref "C26") (pin "1") (pinfunction "1_1") (pintype "passive"))
      (node (ref "C27") (pin "1") (pinfunction "1_1") (pintype "passive"))
      (node (ref "C28") (pin "2") (pinfunction "2_2") (pintype "passive"))
      (node (ref "C29") (pin "1") (pinfunction "1_1") (pintype "passive"))
      (node (ref "JP2") (pin "4") (pinfunction "4_4") (pintype "passive"))
      (node (ref "JP5") (pin "1") (pinfunction "1_1") (pintype "passive"))
      (node (ref "JP5") (pin "2") (pinfunction "2_2") (pintype "passive"))
      (node (ref "R7") (pin "2") (pinfunction "2_2") (pintype "passive"))
      (node (ref "SW1") (pin "2") (pinfunction "2_2") (pintype "passive"))
      (node (ref "SW3") (pin "2") (pinfunction "2_2") (pintype "passive"))
      (node (ref "U4") (pin "4") (pinfunction "GND_4") (pintype "passive"))
      (node (ref "X1") (pin "2") (pinfunction "2_2") (pintype "passive"))
      (node (ref "X1") (pin "4") (pinfunction "4_4") (pintype "passive"))
    )
    (net (code "113") (name "Net-(LED2-K)") (class "Default")
      (node (ref "LED2") (pin "2") (pinfunction "K_2") (pintype "passive"))
      (node (ref "R9") (pin "2") (pinfunction "2_2") (pintype "passive"))
    )
    (net (code "114") (name "Net-(LED3-K)") (class "Default")
      (node (ref "LED3") (pin "2") (pinfunction "K_2") (pintype "passive"))
      (node (ref "R10") (pin "2") (pinfunction "2_2") (pintype "passive"))
    )
    (net (code "115") (name "Net-(U4-CLK)") (class "Default")
      (node (ref "R12") (pin "2") (pinfunction "2_2") (pintype "passive"))
      (node (ref "U4") (pin "6") (pinfunction "CLK_6") (pintype "passive"))
    )
    (net (code "116") (name "VCC_DP_OUT") (class "Default")
      (node (ref "JP2") (pin "2") (pinfunction "2_2") (pintype "passive"))
    )
    (net (code "117") (name "VREFP") (class "Default")
      (node (ref "JP4") (pin "7") (pinfunction "7_7") (pintype "passive"))
    )
  )
)
